# Headphone-Amplifier-ClassAB-alt.net
KiCad netlist of a schematic drawn in EAGLE
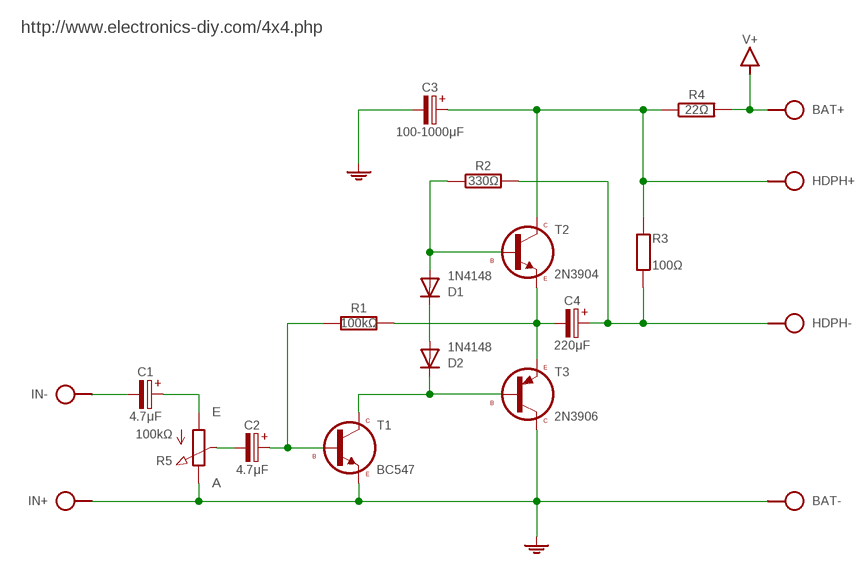
[diagram p0: schematic, sheet 1]

(export (version "E")
  (design (tool "Eeschema 10.0.6"))
  (components
    (comp (ref "BAT")
      (value "SPAD+-+-")
      (footprint "eagle-import:SPAD+-")
      (libsource (lib "eagle-import") (part "SPAD+-+-"))
    )
    (comp (ref "C1")
      (value "4.7μF")
      (footprint "eagle-import:E2,5-3")
      (libsource (lib "eagle-import") (part "CPOLE2,5-3"))
    )
    (comp (ref "C2")
      (value "4.7μF")
      (footprint "eagle-import:E2,5-3")
      (libsource (lib "eagle-import") (part "CPOLE2,5-3"))
    )
    (comp (ref "C3")
      (value "100-1000μF")
      (footprint "eagle-import:E2.5-4_V")
      (libsource (lib "eagle-import") (part "CPOLE2,5-4/V"))
    )
    (comp (ref "C4")
      (value "220μF")
      (footprint "eagle-import:E5-4")
      (libsource (lib "eagle-import") (part "CPOLE5-4"))
    )
    (comp (ref "D1")
      (value "1N4148")
      (footprint "eagle-import:DO34-5-V")
      (libsource (lib "eagle-import") (part "DIODE34-5-V"))
    )
    (comp (ref "D2")
      (value "1N4148")
      (footprint "eagle-import:DO34-5V")
      (libsource (lib "eagle-import") (part "DIODE34-5V"))
    )
    (comp (ref "HDPH")
      (value "SPAD+--+")
      (footprint "eagle-import:SPAD-+")
      (libsource (lib "eagle-import") (part "SPAD+--+"))
    )
    (comp (ref "IN")
      (value "SPAD+-+-")
      (footprint "eagle-import:SPAD+-")
      (libsource (lib "eagle-import") (part "SPAD+-+-"))
    )
    (comp (ref "R1")
      (value "100kΩ")
      (footprint "eagle-import:0204_10")
      (libsource (lib "eagle-import") (part "R-H0204/10"))
    )
    (comp (ref "R2")
      (value "330Ω")
      (footprint "eagle-import:0204_10")
      (libsource (lib "eagle-import") (part "R-H0204/10"))
    )
    (comp (ref "R3")
      (value "100Ω")
      (footprint "eagle-import:0204_10")
      (libsource (lib "eagle-import") (part "R0204/10"))
    )
    (comp (ref "R4")
      (value "22Ω")
      (footprint "eagle-import:0204_10")
      (libsource (lib "eagle-import") (part "R-H0204/10"))
    )
    (comp (ref "R5")
      (value "100kΩ")
      (footprint "eagle-import:CONN-3P")
      (libsource (lib "eagle-import") (part "POT-3P"))
    )
    (comp (ref "T1")
      (value "BC547")
      (footprint "eagle-import:TO92")
      (libsource (lib "eagle-import") (part "2N3904"))
    )
    (comp (ref "T2")
      (value "2N3904")
      (footprint "eagle-import:TO92")
      (libsource (lib "eagle-import") (part "2N3904"))
    )
    (comp (ref "T3")
      (value "2N3906")
      (footprint "eagle-import:TO92")
      (libsource (lib "eagle-import") (part "2N3906"))
    )
  )
  (nets
    (net (code "1") (name "GND") (class "Default")
      (node (ref "BAT") (pin "1") (pinfunction "P$1_1") (pintype "passive"))
      (node (ref "C3") (pin "-") (pinfunction "-_-") (pintype "passive"))
      (node (ref "IN") (pin "2") (pinfunction "P$1_2") (pintype "passive"))
      (node (ref "R5") (pin "3") (pinfunction "E_3") (pintype "passive"))
      (node (ref "T1") (pin "1") (pinfunction "E_1") (pintype "passive"))
      (node (ref "T3") (pin "3") (pinfunction "C_3") (pintype "passive"))
    )
    (net (code "2") (name "Net-(D1-PadC)") (class "Default")
      (node (ref "D1") (pin "C") (pinfunction "C_C") (pintype "passive"))
      (node (ref "D2") (pin "A") (pinfunction "A_A") (pintype "passive"))
    )
    (net (code "3") (name "Net-(HDPHA-P$1)") (class "Default")
      (node (ref "C3") (pin "+") (pinfunction "+_+") (pintype "passive"))
      (node (ref "HDPH") (pin "2") (pinfunction "P$1_2") (pintype "passive"))
      (node (ref "R3") (pin "1") (pinfunction "2_1") (pintype "passive"))
      (node (ref "R4") (pin "1") (pinfunction "1_1") (pintype "passive"))
      (node (ref "T2") (pin "3") (pinfunction "C_3") (pintype "passive"))
    )
    (net (code "4") (name "Net-(HDPHB-P$1)") (class "Default")
      (node (ref "C4") (pin "+") (pinfunction "+_+") (pintype "passive"))
      (node (ref "HDPH") (pin "1") (pinfunction "P$1_1") (pintype "passive"))
      (node (ref "R2") (pin "2") (pinfunction "2_2") (pintype "passive"))
      (node (ref "R3") (pin "2") (pinfunction "1_2") (pintype "passive"))
    )
    (net (code "5") (name "Net-(INB-P$1)") (class "Default")
      (node (ref "C1") (pin "-") (pinfunction "-_-") (pintype "passive"))
      (node (ref "IN") (pin "1") (pinfunction "P$1_1") (pintype "passive"))
    )
    (net (code "6") (name "Net-(R5-A)") (class "Default")
      (node (ref "C1") (pin "+") (pinfunction "+_+") (pintype "passive"))
      (node (ref "R5") (pin "1") (pinfunction "A_1") (pintype "passive"))
    )
    (net (code "7") (name "Net-(R5-S)") (class "Default")
      (node (ref "C2") (pin "-") (pinfunction "-_-") (pintype "passive"))
      (node (ref "R5") (pin "2") (pinfunction "S_2") (pintype "passive"))
    )
    (net (code "8") (name "Net-(T1-B)") (class "Default")
      (node (ref "C2") (pin "+") (pinfunction "+_+") (pintype "passive"))
      (node (ref "R1") (pin "1") (pinfunction "1_1") (pintype "passive"))
      (node (ref "T1") (pin "2") (pinfunction "B_2") (pintype "passive"))
    )
    (net (code "9") (name "Net-(T1-C)") (class "Default")
      (node (ref "D2") (pin "C") (pinfunction "C_C") (pintype "passive"))
      (node (ref "T1") (pin "3") (pinfunction "C_3") (pintype "passive"))
      (node (ref "T3") (pin "2") (pinfunction "B_2") (pintype "passive"))
    )
    (net (code "10") (name "Net-(T2-B)") (class "Default")
      (node (ref "D1") (pin "A") (pinfunction "A_A") (pintype "passive"))
      (node (ref "R2") (pin "1") (pinfunction "1_1") (pintype "passive"))
      (node (ref "T2") (pin "2") (pinfunction "B_2") (pintype "passive"))
    )
    (net (code "11") (name "Net-(T2-E)") (class "Default")
      (node (ref "C4") (pin "-") (pinfunction "-_-") (pintype "passive"))
      (node (ref "R1") (pin "2") (pinfunction "2_2") (pintype "passive"))
      (node (ref "T2") (pin "1") (pinfunction "E_1") (pintype "passive"))
      (node (ref "T3") (pin "1") (pinfunction "E_1") (pintype "passive"))
    )
    (net (code "12") (name "V+") (class "Default")
      (node (ref "BAT") (pin "2") (pinfunction "P$1_2") (pintype "passive"))
      (node (ref "R4") (pin "2") (pinfunction "2_2") (pintype "passive"))
    )
  )
)
